# F4AIR.net
KiCad netlist of a schematic drawn in Altium Designer
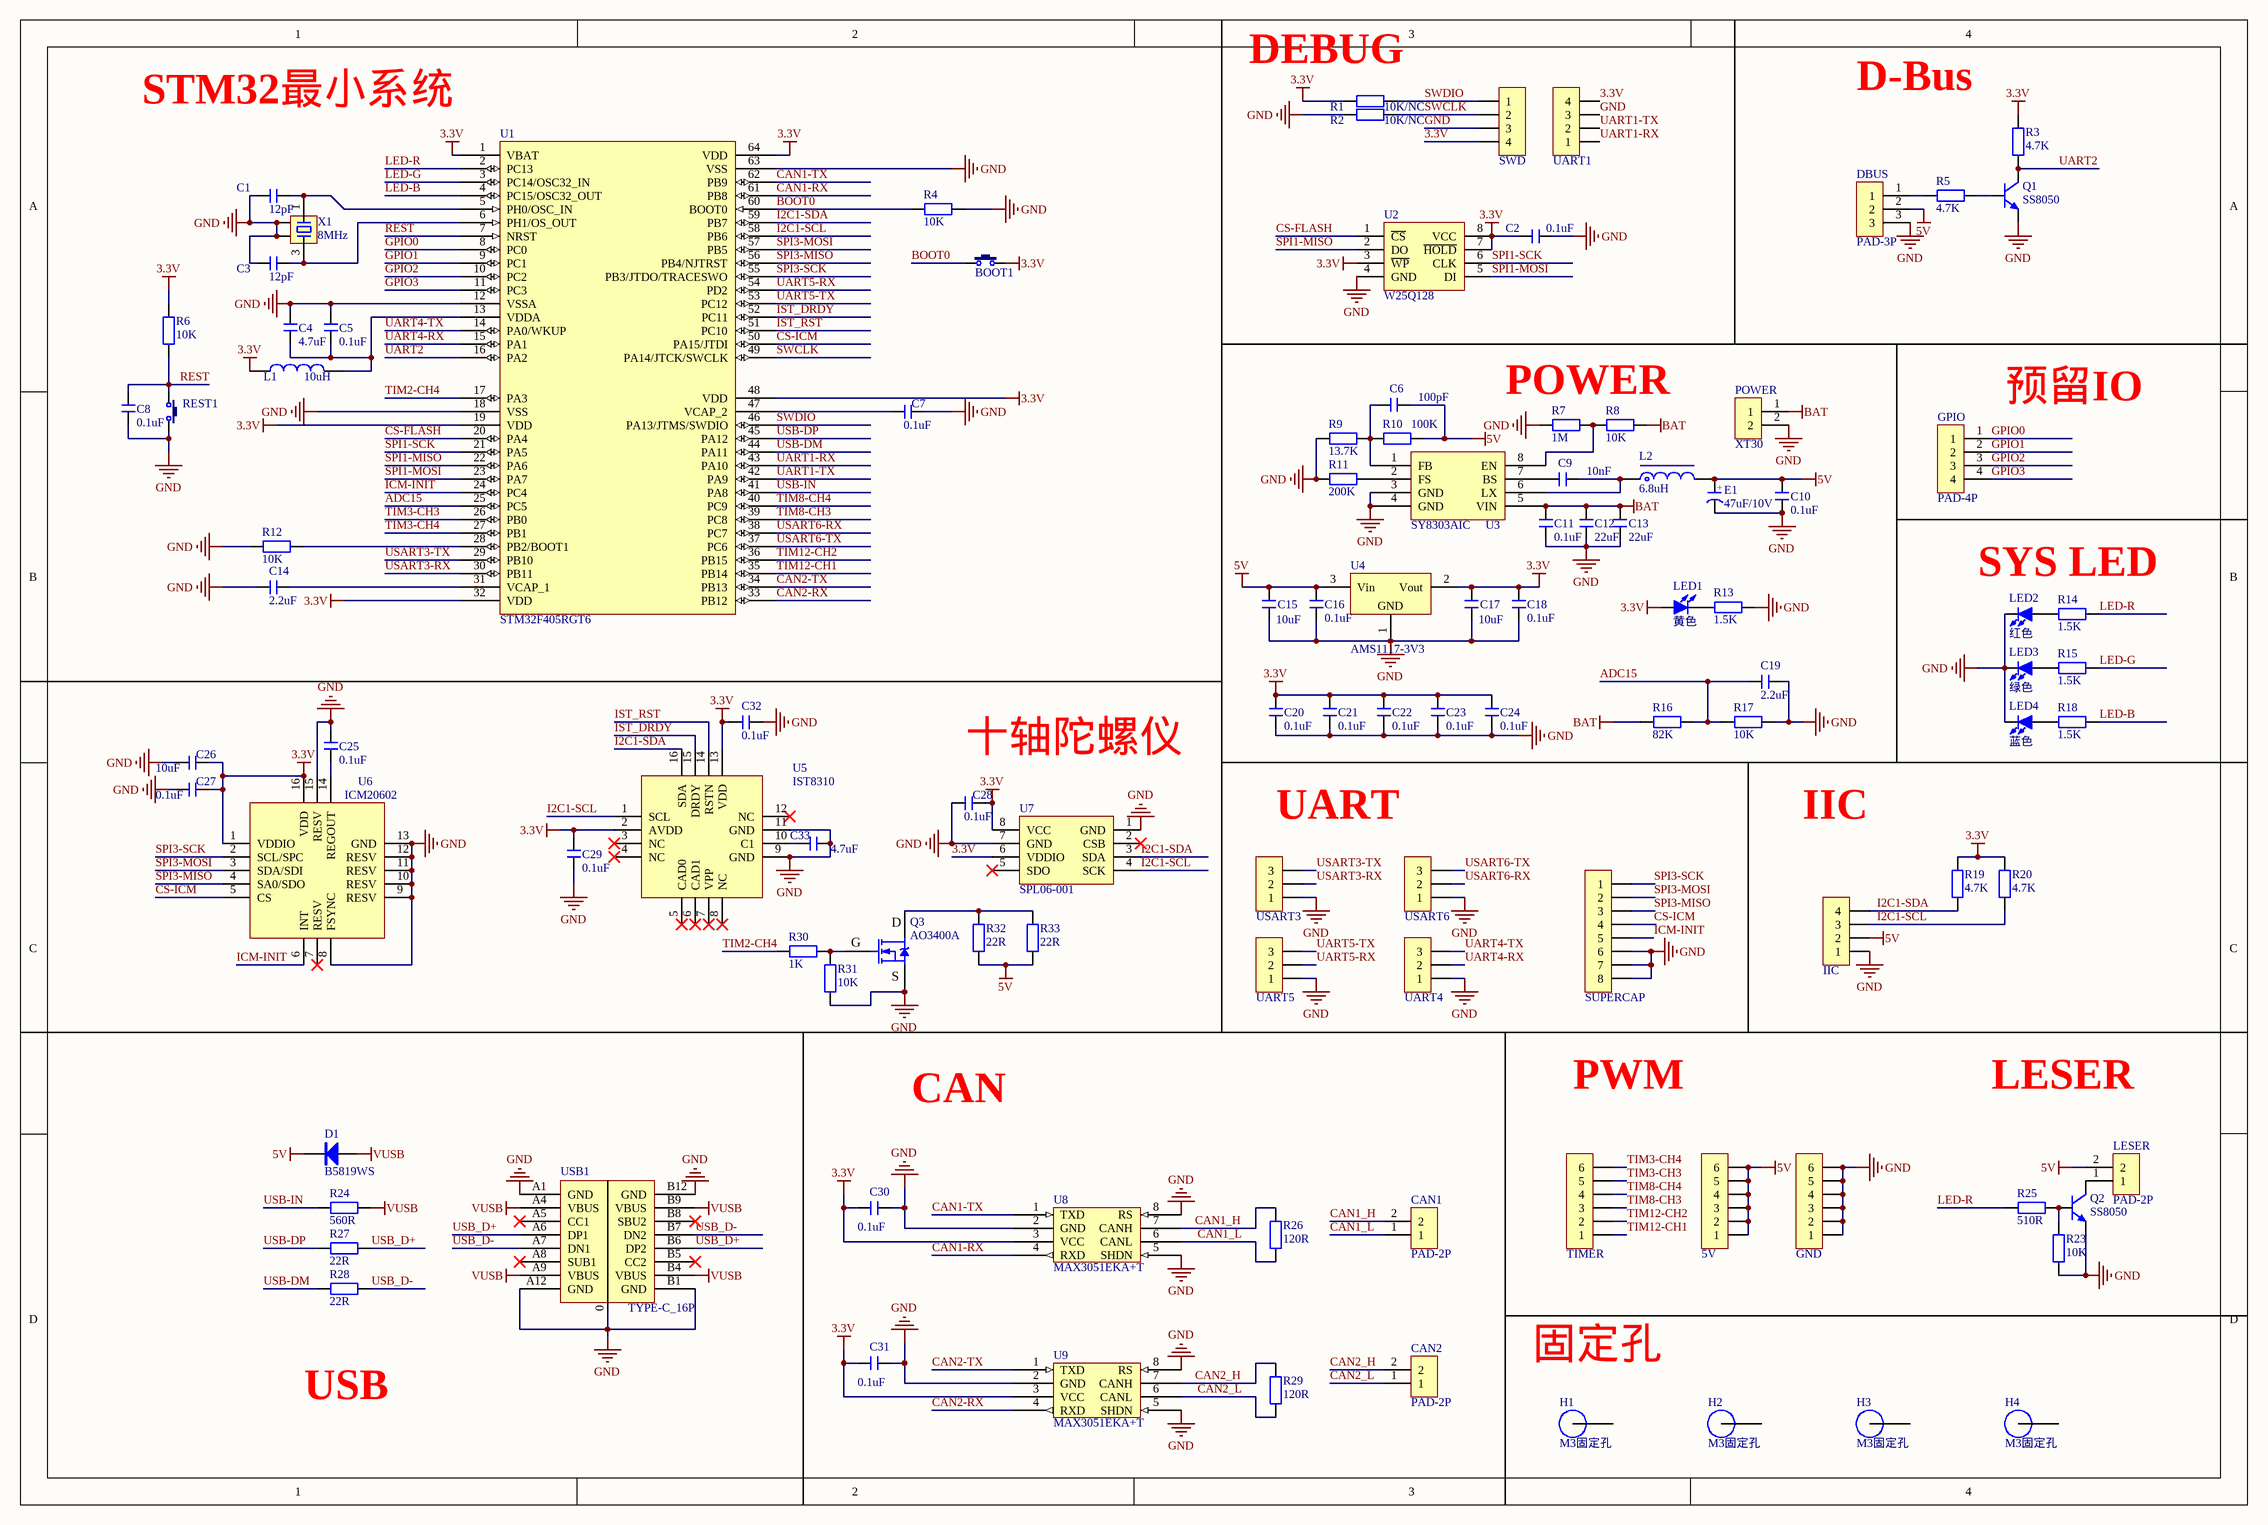
[diagram p0: F4AIR.SchDoc]

(export (version "E")
  (design (tool "Eeschema 10.0.6"))
  (components
    (comp (ref "5V")
      (value "HDR-1X6")
      (footprint "HDR2.54-LI-6P")
      (description "6P接插件")
      (libsource (lib "*") (part "Header 6"))
    )
    (comp (ref "BOOT1")
      (value "3x6x5")
      (footprint "TSW SMD-3*6*5")
      (description "3x6轻触开关")
      (libsource (lib "") (part "TSW 3x6_1"))
    )
    (comp (ref "C1")
      (value "12pF")
      (footprint "C 0603_M")
      (description "无极性贴片电容")
      (libsource (lib "Schlib1") (part "C"))
    )
    (comp (ref "C2")
      (value "0.1uF")
      (footprint "C 0603_M")
      (description "无极性贴片电容")
      (libsource (lib "Schlib") (part "C"))
    )
    (comp (ref "C3")
      (value "12pF")
      (footprint "C 0603_M")
      (description "无极性贴片电容")
      (libsource (lib "Schlib1") (part "C"))
    )
    (comp (ref "C4")
      (value "4.7uF")
      (footprint "C 0603_M")
      (description "无极性贴片电容")
      (libsource (lib "Schlib1") (part "C"))
    )
    (comp (ref "C5")
      (value "0.1uF")
      (footprint "C 0603_M")
      (description "无极性贴片电容")
      (libsource (lib "Schlib1") (part "C"))
    )
    (comp (ref "C6")
      (value "100pF")
      (footprint "C 0603_M")
      (description "无极性贴片电容")
      (libsource (lib "Schlib1") (part "C"))
    )
    (comp (ref "C7")
      (value "0.1uF")
      (footprint "C 0603_M")
      (description "无极性贴片电容")
      (libsource (lib "Schlib1") (part "C"))
    )
    (comp (ref "C8")
      (value "0.1uF")
      (footprint "C 0603_M")
      (description "无极性贴片电容")
      (libsource (lib "Schlib1") (part "C"))
    )
    (comp (ref "C9")
      (value "10nF")
      (footprint "C 0603_M")
      (description "无极性贴片电容")
      (libsource (lib "Schlib1") (part "C"))
    )
    (comp (ref "C10")
      (value "0.1uF")
      (footprint "C 0603_M")
      (description "无极性贴片电容")
      (libsource (lib "Schlib1") (part "C"))
    )
    (comp (ref "C11")
      (value "0.1uF")
      (footprint "C 0603_M")
      (description "无极性贴片电容")
      (libsource (lib "Schlib1") (part "C"))
    )
    (comp (ref "C12")
      (value "22uF")
      (footprint "C 1210_M")
      (description "无极性贴片电容")
      (libsource (lib "核心板v2") (part "C"))
    )
    (comp (ref "C13")
      (value "22uF")
      (footprint "C 1210_M")
      (description "无极性贴片电容")
      (libsource (lib "核心板v2") (part "C"))
    )
    (comp (ref "C14")
      (value "2.2uF")
      (footprint "C 0603_M")
      (description "无极性贴片电容")
      (libsource (lib "Schlib1") (part "C"))
    )
    (comp (ref "C15")
      (value "10uF")
      (footprint "C 0805_M")
      (description "无极性贴片电容")
      (libsource (lib "altium-import") (part "root_1_C_"))
    )
    (comp (ref "C16")
      (value "0.1uF")
      (footprint "C 0603_M")
      (description "无极性贴片电容")
      (libsource (lib "Schlib1") (part "C"))
    )
    (comp (ref "C17")
      (value "10uF")
      (footprint "C 0805_M")
      (description "无极性贴片电容")
      (libsource (lib "altium-import") (part "root_1_C_"))
    )
    (comp (ref "C18")
      (value "0.1uF")
      (footprint "C 0603_M")
      (description "无极性贴片电容")
      (libsource (lib "Schlib1") (part "C"))
    )
    (comp (ref "C19")
      (value "2.2uF")
      (footprint "C 0603_M")
      (description "无极性贴片电容")
      (libsource (lib "Schlib") (part "C"))
    )
    (comp (ref "C20")
      (value "0.1uF")
      (footprint "C 0603_M")
      (description "无极性贴片电容")
      (libsource (lib "Schlib1") (part "C"))
    )
    (comp (ref "C21")
      (value "0.1uF")
      (footprint "C 0603_M")
      (description "无极性贴片电容")
      (libsource (lib "Schlib1") (part "C"))
    )
    (comp (ref "C22")
      (value "0.1uF")
      (footprint "C 0603_M")
      (description "无极性贴片电容")
      (libsource (lib "Schlib1") (part "C"))
    )
    (comp (ref "C23")
      (value "0.1uF")
      (footprint "C 0603_M")
      (description "无极性贴片电容")
      (libsource (lib "Schlib1") (part "C"))
    )
    (comp (ref "C24")
      (value "0.1uF")
      (footprint "C 0603_M")
      (description "无极性贴片电容")
      (libsource (lib "Schlib1") (part "C"))
    )
    (comp (ref "C25")
      (value "0.1uF")
      (footprint "C 0603_M")
      (description "无极性贴片电容")
      (libsource (lib "Schlib1") (part "C"))
    )
    (comp (ref "C26")
      (value "10uF")
      (footprint "C 0805_M")
      (description "无极性贴片电容")
      (libsource (lib "Schlib1") (part "C"))
    )
    (comp (ref "C27")
      (value "0.1uF")
      (footprint "C 0603_M")
      (description "无极性贴片电容")
      (libsource (lib "Schlib1") (part "C"))
    )
    (comp (ref "C28")
      (value "0.1uF")
      (footprint "C 0603_M")
      (description "无极性贴片电容")
      (libsource (lib "Schlib1") (part "C"))
    )
    (comp (ref "C29")
      (value "0.1uF")
      (footprint "C 0603_M")
      (description "无极性贴片电容")
      (libsource (lib "Schlib1") (part "C"))
    )
    (comp (ref "C30")
      (value "0.1uF")
      (footprint "C 0603_M")
      (description "无极性贴片电容")
      (libsource (lib "Schlib1") (part "C"))
    )
    (comp (ref "C31")
      (value "0.1uF")
      (footprint "C 0603_M")
      (description "无极性贴片电容")
      (libsource (lib "Schlib1") (part "C"))
    )
    (comp (ref "C32")
      (value "0.1uF")
      (footprint "C 0603_M")
      (description "无极性贴片电容")
      (libsource (lib "Schlib1") (part "C"))
    )
    (comp (ref "C33")
      (value "4.7uF")
      (footprint "C 0603_M")
      (description "无极性贴片电容")
      (libsource (lib "Schlib1") (part "C"))
    )
    (comp (ref "CAN1") (value "PAD-2P") (footprint "MX 1.25-WS-2P") (libsource (lib "") (part "PAD-2P_1")))
    (comp (ref "CAN2") (value "PAD-2P") (footprint "MX 1.25-WS-2P") (libsource (lib "") (part "PAD-2P_1")))
    (comp (ref "D1")
      (value "B5819WS")
      (footprint "SOD-323")
      (description "肖特基二极管")
      (libsource (lib "Schlib") (part "SS54"))
    )
    (comp (ref "DBUS") (value "PAD-3P") (footprint "HDR2.54-WI-3P") (libsource (lib "F4AIR") (part "PAD-3P")))
    (comp (ref "E1")
      (value "47uF/10V")
      (footprint "CD A(3216)")
      (description "贴片钽电容")
      (libsource (lib "核心板v2") (part "C-CD"))
    )
    (comp (ref "GND")
      (value "HDR-1X6")
      (footprint "HDR2.54-LI-6P")
      (description "6P接插件")
      (libsource (lib "*") (part "Header 6"))
    )
    (comp (ref "GPIO") (value "PAD-4P") (footprint "PAD-1.25-4P") (libsource (lib "F4AIR") (part "PAD-4P")))
    (comp (ref "H1")
      (value "M3固定孔")
      (footprint "M3x4_N")
      (description "铜柱孔")
      (libsource (lib "F4AIR") (part "M3"))
    )
    (comp (ref "H2")
      (value "M3固定孔")
      (footprint "M3x4_N")
      (description "铜柱孔")
      (libsource (lib "F4AIR") (part "M3"))
    )
    (comp (ref "H3")
      (value "M3固定孔")
      (footprint "M3x4_N")
      (description "铜柱孔")
      (libsource (lib "F4AIR") (part "M3"))
    )
    (comp (ref "H4")
      (value "M3固定孔")
      (footprint "M3x4_N")
      (description "铜柱孔")
      (libsource (lib "F4AIR") (part "M3"))
    )
    (comp (ref "IIC")
      (value "HDR-1X4")
      (footprint "HDR2.54-LI-4P")
      (description "HDR 2.54 -4P")
      (libsource (lib "核心板v2") (part "HDR 2.54 -4P_1"))
    )
    (comp (ref "L1")
      (value "10uH")
      (footprint "L 0603")
      (description "小功率贴片电感")
      (libsource (lib "Schlib1") (part "L"))
    )
    (comp (ref "L2")
      (value "6.8uH")
      (footprint "L-SMD-0630")
      (description "贴片功率电感")
      (libsource (lib "核心板v2") (part "L-CD"))
    )
    (comp (ref "LED1")
      (value "黄色")
      (footprint "LED 0603Y")
      (description "贴片LED")
      (libsource (lib "核心板v2") (part "LED-SMD"))
    )
    (comp (ref "LED2")
      (value "红色")
      (footprint "LED 0603R")
      (description "贴片LED")
      (libsource (lib "核心板v2") (part "LED-SMD"))
    )
    (comp (ref "LED3")
      (value "绿色")
      (footprint "LED 0603G")
      (description "贴片LED")
      (libsource (lib "核心板v2") (part "LED-SMD"))
    )
    (comp (ref "LED4")
      (value "蓝色")
      (footprint "LED 0603B")
      (description "贴片LED")
      (libsource (lib "核心板v2") (part "LED-SMD"))
    )
    (comp (ref "LESER") (value "PAD-2P") (footprint "MX 1.25-WS-2P") (libsource (lib "") (part "PAD-2P_1")))
    (comp (ref "POWER") (value "XT30") (footprint "XT30-L") (libsource (lib "F4AIR") (part "PAD-2P")))
    (comp (ref "Q1")
      (value "SS8050")
      (footprint "SOT23-3M")
      (description "高频放大-NPN型")
      (libsource (lib "Schlib1") (part "8050-SMD"))
    )
    (comp (ref "Q2")
      (value "SS8050")
      (footprint "SOT23-3M")
      (description "高频放大-NPN型")
      (libsource (lib "核心板v2") (part "8050-SMD"))
    )
    (comp (ref "Q3") (value "AO3400A") (footprint "SOT23-3M") (libsource (lib "F4AIR") (part "AO3400A")))
    (comp (ref "R1")
      (value "10K/NC")
      (footprint "R 0603_M")
      (description "贴片电阻")
      (libsource (lib "Schlib1") (part "R"))
    )
    (comp (ref "R2")
      (value "10K/NC")
      (footprint "R 0603_M")
      (description "贴片电阻")
      (libsource (lib "Schlib1") (part "R"))
    )
    (comp (ref "R3")
      (value "4.7K")
      (footprint "R 0603_M")
      (description "贴片电阻")
      (libsource (lib "Schlib1") (part "R"))
    )
    (comp (ref "R4")
      (value "10K")
      (footprint "R 0603_M")
      (description "贴片电阻")
      (libsource (lib "Schlib1") (part "R"))
    )
    (comp (ref "R5")
      (value "4.7K")
      (footprint "R 0603_M")
      (description "贴片电阻")
      (libsource (lib "Schlib1") (part "R"))
    )
    (comp (ref "R6")
      (value "10K")
      (footprint "R 0603_M")
      (description "贴片电阻")
      (libsource (lib "Schlib1") (part "R"))
    )
    (comp (ref "R7")
      (value "1M")
      (footprint "R 0603_M")
      (description "贴片电阻")
      (libsource (lib "altium-import") (part "root_2_R_"))
    )
    (comp (ref "R8")
      (value "10K")
      (footprint "R 0603_M")
      (description "贴片电阻")
      (libsource (lib "altium-import") (part "root_2_R_"))
    )
    (comp (ref "R9")
      (value "13.7K")
      (footprint "R 0603_M")
      (description "贴片电阻")
      (libsource (lib "altium-import") (part "root_2_R_"))
    )
    (comp (ref "R10")
      (value "100K")
      (footprint "R 0603_M")
      (description "贴片电阻")
      (libsource (lib "altium-import") (part "root_2_R_"))
    )
    (comp (ref "R11")
      (value "200K")
      (footprint "R 0603_M")
      (description "贴片电阻")
      (libsource (lib "altium-import") (part "root_2_R_"))
    )
    (comp (ref "R12")
      (value "10K")
      (footprint "R 0603_M")
      (description "贴片电阻")
      (libsource (lib "Schlib1") (part "R"))
    )
    (comp (ref "R13")
      (value "1.5K")
      (footprint "R 0603_M")
      (description "贴片电阻")
      (libsource (lib "核心板v2") (part "R"))
    )
    (comp (ref "R14")
      (value "1.5K")
      (footprint "R 0603_M")
      (description "贴片电阻")
      (libsource (lib "核心板v2") (part "R"))
    )
    (comp (ref "R15")
      (value "1.5K")
      (footprint "R 0603_M")
      (description "贴片电阻")
      (libsource (lib "核心板v2") (part "R"))
    )
    (comp (ref "R16")
      (value "82K")
      (footprint "R 0603_M")
      (description "贴片电阻")
      (libsource (lib "Schlib") (part "R"))
    )
    (comp (ref "R17")
      (value "10K")
      (footprint "R 0603_M")
      (description "贴片电阻")
      (libsource (lib "Schlib") (part "R"))
    )
    (comp (ref "R18")
      (value "1.5K")
      (footprint "R 0603_M")
      (description "贴片电阻")
      (libsource (lib "核心板v2") (part "R"))
    )
    (comp (ref "R19")
      (value "4.7K")
      (footprint "R 0603_M")
      (description "贴片电阻")
      (libsource (lib "altium-import") (part "root_3_R_"))
    )
    (comp (ref "R20")
      (value "4.7K")
      (footprint "R 0603_M")
      (description "贴片电阻")
      (libsource (lib "altium-import") (part "root_1_R_"))
    )
    (comp (ref "R23")
      (value "10K")
      (footprint "R 0603_M")
      (description "贴片电阻")
      (libsource (lib "核心板v2") (part "R"))
    )
    (comp (ref "R24")
      (value "560R")
      (footprint "R 0603_M")
      (description "贴片电阻")
      (libsource (lib "Schlib1") (part "R"))
    )
    (comp (ref "R25")
      (value "510R")
      (footprint "R 0603_M")
      (description "贴片电阻")
      (libsource (lib "核心板v2") (part "R"))
    )
    (comp (ref "R26")
      (value "120R")
      (footprint "R 0603_M")
      (description "贴片电阻")
      (libsource (lib "altium-import") (part "root_1_R_"))
    )
    (comp (ref "R27")
      (value "22R")
      (footprint "R 0603_M")
      (description "贴片电阻")
      (libsource (lib "Schlib") (part "R"))
    )
    (comp (ref "R28")
      (value "22R")
      (footprint "R 0603_M")
      (description "贴片电阻")
      (libsource (lib "Schlib") (part "R"))
    )
    (comp (ref "R29")
      (value "120R")
      (footprint "R 0603_M")
      (description "贴片电阻")
      (libsource (lib "altium-import") (part "root_1_R_"))
    )
    (comp (ref "R30")
      (value "1K")
      (footprint "R 0603_M")
      (description "贴片电阻")
      (libsource (lib "F4AIR") (part "R"))
    )
    (comp (ref "R31")
      (value "10K")
      (footprint "R 0603_M")
      (description "贴片电阻")
      (libsource (lib "F4AIR") (part "R"))
    )
    (comp (ref "R32")
      (value "22R")
      (footprint "R 0603_M")
      (description "贴片电阻")
      (libsource (lib "F4AIR") (part "R"))
    )
    (comp (ref "R33")
      (value "22R")
      (footprint "R 0603_M")
      (description "贴片电阻")
      (libsource (lib "F4AIR") (part "R"))
    )
    (comp (ref "REST1")
      (value "3x6x5")
      (footprint "TSW SMD-3*6*5")
      (description "3x6轻触开关")
      (libsource (lib "Schlib1") (part "TSW 3x6"))
    )
    (comp (ref "SUPERCAP")
      (value "HDR-1X8")
      (footprint "MX 1.25-WS-6P")
      (description "HDR 2.54 -8P")
      (libsource (lib "cap") (part "HDR 2.54 -8P"))
    )
    (comp (ref "SWD")
      (value "HDR-1X4")
      (footprint "MX 1.25-WS-4P")
      (description "MX 1.25 -4P")
      (libsource (lib "Schlib1") (part "MX 1.25 -4P"))
    )
    (comp (ref "TIMER")
      (value "HDR-1X6")
      (footprint "HDR2.54-LI-6P")
      (description "6P接插件")
      (libsource (lib "*") (part "Header 6"))
    )
    (comp (ref "U1")
      (value "STM32F405RGT6")
      (footprint "LQFP64")
      (libsource (lib "Schlib") (part "STM32F405RGT6"))
    )
    (comp (ref "U2")
      (value "W25Q128")
      (footprint "SOP8_M - 208mil")
      (libsource (lib "Schlib") (part "W25Q128"))
    )
    (comp (ref "U3")
      (value "SY8303AIC")
      (footprint "SOT23-8")
      (description "DCDC降压芯片")
      (libsource (lib "核心板v2") (part "SY8303AIC"))
    )
    (comp (ref "U4")
      (value "AMS1117-3V3")
      (footprint "SOT-89")
      (description "三端稳压芯片")
      (libsource (lib "F4AIR") (part "AMS1117"))
    )
    (comp (ref "U5")
      (value "IST8310")
      (footprint "LGA16 3x3")
      (description "三轴电子罗盘")
      (libsource (lib "F4AIR") (part "IST8310"))
    )
    (comp (ref "U6") (value "ICM20602") (footprint "LGA16") (libsource (lib "Schlib1") (part "ICM20602")))
    (comp (ref "U7") (value "SPL06-001") (footprint "LGA08") (libsource (lib "Schlib1") (part "SPL06")))
    (comp (ref "U8")
      (value "MAX3051EKA+T")
      (footprint "SOT23-8")
      (description "CAN芯片")
      (libsource (lib "核心板v2") (part "MAX3051EKA+T"))
    )
    (comp (ref "U9")
      (value "MAX3051EKA+T")
      (footprint "SOT23-8")
      (description "CAN芯片")
      (libsource (lib "核心板v2") (part "MAX3051EKA+T"))
    )
    (comp (ref "UART1")
      (value "HDR-1X4")
      (footprint "MX 1.25-WS-4P")
      (description "HDR 2.54 -4P")
      (libsource (lib "核心板v2") (part "HDR 2.54 -4P_1"))
    )
    (comp (ref "UART4")
      (value "HDR-1X3")
      (footprint "MX 1.25-WS-3P")
      (description "HDR 2.54 -3P")
      (libsource (lib "Schlib1") (part "HDR 2.54 -3P"))
    )
    (comp (ref "UART5")
      (value "HDR-1X3")
      (footprint "MX 1.25-WS-3P")
      (description "HDR 2.54 -3P")
      (libsource (lib "Schlib1") (part "HDR 2.54 -3P"))
    )
    (comp (ref "USART3")
      (value "HDR-1X3")
      (footprint "MX 1.25-WS-3P")
      (description "HDR 2.54 -3P")
      (libsource (lib "Schlib1") (part "HDR 2.54 -3P"))
    )
    (comp (ref "USART6")
      (value "HDR-1X3")
      (footprint "MX 1.25-WS-3P")
      (description "HDR 2.54 -3P")
      (libsource (lib "Schlib1") (part "HDR 2.54 -3P"))
    )
    (comp (ref "USB1")
      (value "TYPE-C_16P")
      (footprint "Type-C_16p")
      (libsource (lib "Schlib") (part "TYPE-C_16P"))
    )
    (comp (ref "X1")
      (value "8MHz")
      (footprint "OSC 3225-4P")
      (description "4脚无源晶振")
      (libsource (lib "Schlib1") (part "XTAL-4P"))
    )
  )
  (nets
    (net (code "1") (name "/ADC15") (class "Default")
      (node (ref "C19") (pin "1") (pinfunction "1_1") (pintype "passive"))
      (node (ref "R16") (pin "2") (pinfunction "2_2") (pintype "passive"))
      (node (ref "R17") (pin "1") (pinfunction "1_1") (pintype "passive"))
      (node (ref "U1") (pin "25") (pinfunction "PC5_25") (pintype "bidirectional"))
    )
    (net (code "2") (name "/BOOT0") (class "Default")
      (node (ref "BOOT1") (pin "1") (pinfunction "1_1") (pintype "passive"))
      (node (ref "R4") (pin "1") (pinfunction "1_1") (pintype "passive"))
      (node (ref "U1") (pin "60") (pinfunction "BOOT0_60") (pintype "input"))
    )
    (net (code "3") (name "/CAN1-RX") (class "Default")
      (node (ref "U1") (pin "61") (pinfunction "PB8_61") (pintype "bidirectional"))
      (node (ref "U8") (pin "4") (pinfunction "RXD_4") (pintype "output"))
    )
    (net (code "4") (name "/CAN1-TX") (class "Default")
      (node (ref "U1") (pin "62") (pinfunction "PB9_62") (pintype "bidirectional"))
      (node (ref "U8") (pin "1") (pinfunction "TXD_1") (pintype "input"))
    )
    (net (code "5") (name "/CAN1_H") (class "Default")
      (node (ref "CAN1") (pin "2") (pinfunction "2_2") (pintype "passive"))
      (node (ref "R26") (pin "2") (pinfunction "2_2") (pintype "passive"))
      (node (ref "U8") (pin "7") (pinfunction "CANH_7") (pintype "passive"))
    )
    (net (code "6") (name "/CAN1_L") (class "Default")
      (node (ref "CAN1") (pin "1") (pinfunction "1_1") (pintype "passive"))
      (node (ref "R26") (pin "1") (pinfunction "1_1") (pintype "passive"))
      (node (ref "U8") (pin "6") (pinfunction "CANL_6") (pintype "passive"))
    )
    (net (code "7") (name "/CAN2-RX") (class "Default")
      (node (ref "U1") (pin "33") (pinfunction "PB12_33") (pintype "bidirectional"))
      (node (ref "U9") (pin "4") (pinfunction "RXD_4") (pintype "output"))
    )
    (net (code "8") (name "/CAN2-TX") (class "Default")
      (node (ref "U1") (pin "34") (pinfunction "PB13_34") (pintype "bidirectional"))
      (node (ref "U9") (pin "1") (pinfunction "TXD_1") (pintype "input"))
    )
    (net (code "9") (name "/CAN2_H") (class "Default")
      (node (ref "CAN2") (pin "2") (pinfunction "2_2") (pintype "passive"))
      (node (ref "R29") (pin "2") (pinfunction "2_2") (pintype "passive"))
      (node (ref "U9") (pin "7") (pinfunction "CANH_7") (pintype "passive"))
    )
    (net (code "10") (name "/CAN2_L") (class "Default")
      (node (ref "CAN2") (pin "1") (pinfunction "1_1") (pintype "passive"))
      (node (ref "R29") (pin "1") (pinfunction "1_1") (pintype "passive"))
      (node (ref "U9") (pin "6") (pinfunction "CANL_6") (pintype "passive"))
    )
    (net (code "11") (name "/CS-FLASH") (class "Default")
      (node (ref "U1") (pin "20") (pinfunction "PA4_20") (pintype "bidirectional"))
      (node (ref "U2") (pin "1") (pinfunction "~{CS}_1") (pintype "passive"))
    )
    (net (code "12") (name "/CS-ICM") (class "Default")
      (node (ref "SUPERCAP") (pin "4") (pinfunction "4_4") (pintype "passive"))
      (node (ref "U1") (pin "50") (pinfunction "PA15/JTDI_50") (pintype "bidirectional"))
      (node (ref "U6") (pin "5") (pinfunction "CS_5") (pintype "passive"))
    )
    (net (code "13") (name "/GPIO0") (class "Default")
      (node (ref "GPIO") (pin "1") (pinfunction "1_1") (pintype "passive"))
      (node (ref "U1") (pin "8") (pinfunction "PC0_8") (pintype "bidirectional"))
    )
    (net (code "14") (name "/GPIO1") (class "Default")
      (node (ref "GPIO") (pin "2") (pinfunction "2_2") (pintype "passive"))
      (node (ref "U1") (pin "9") (pinfunction "PC1_9") (pintype "bidirectional"))
    )
    (net (code "15") (name "/GPIO2") (class "Default")
      (node (ref "GPIO") (pin "3") (pinfunction "3_3") (pintype "passive"))
      (node (ref "U1") (pin "10") (pinfunction "PC2_10") (pintype "bidirectional"))
    )
    (net (code "16") (name "/GPIO3") (class "Default")
      (node (ref "GPIO") (pin "4") (pinfunction "4_4") (pintype "passive"))
      (node (ref "U1") (pin "11") (pinfunction "PC3_11") (pintype "bidirectional"))
    )
    (net (code "17") (name "/I2C1-SCL") (class "Default")
      (node (ref "IIC") (pin "3") (pinfunction "3_3") (pintype "passive"))
      (node (ref "R20") (pin "1") (pinfunction "1_1") (pintype "passive"))
      (node (ref "U1") (pin "58") (pinfunction "PB6_58") (pintype "bidirectional"))
      (node (ref "U5") (pin "1") (pinfunction "SCL_1") (pintype "passive"))
      (node (ref "U7") (pin "4") (pinfunction "SCK_4") (pintype "passive"))
    )
    (net (code "18") (name "/I2C1-SDA") (class "Default")
      (node (ref "IIC") (pin "4") (pinfunction "4_4") (pintype "passive"))
      (node (ref "R19") (pin "2") (pinfunction "2_2") (pintype "passive"))
      (node (ref "U1") (pin "59") (pinfunction "PB7_59") (pintype "bidirectional"))
      (node (ref "U5") (pin "16") (pinfunction "SDA_16") (pintype "passive"))
      (node (ref "U7") (pin "3") (pinfunction "SDA_3") (pintype "passive"))
    )
    (net (code "19") (name "/ICM-INIT") (class "Default")
      (node (ref "SUPERCAP") (pin "5") (pinfunction "5_5") (pintype "passive"))
      (node (ref "U1") (pin "24") (pinfunction "PC4_24") (pintype "bidirectional"))
      (node (ref "U6") (pin "6") (pinfunction "INT_6") (pintype "passive"))
    )
    (net (code "20") (name "/IST_DRDY") (class "Default")
      (node (ref "U1") (pin "52") (pinfunction "PC11_52") (pintype "bidirectional"))
      (node (ref "U5") (pin "15") (pinfunction "DRDY_15") (pintype "passive"))
    )
    (net (code "21") (name "/IST_RST") (class "Default")
      (node (ref "U1") (pin "51") (pinfunction "PC10_51") (pintype "bidirectional"))
      (node (ref "U5") (pin "14") (pinfunction "RSTN_14") (pintype "passive"))
    )
    (net (code "22") (name "/LED-B") (class "Default")
      (node (ref "R18") (pin "2") (pinfunction "2_2") (pintype "passive"))
      (node (ref "U1") (pin "4") (pinfunction "PC15/OSC32_OUT_4") (pintype "bidirectional"))
    )
    (net (code "23") (name "/LED-G") (class "Default")
      (node (ref "R15") (pin "2") (pinfunction "2_2") (pintype "passive"))
      (node (ref "U1") (pin "3") (pinfunction "PC14/OSC32_IN_3") (pintype "bidirectional"))
    )
    (net (code "24") (name "/LED-R") (class "Default")
      (node (ref "R14") (pin "2") (pinfunction "2_2") (pintype "passive"))
      (node (ref "R25") (pin "1") (pinfunction "1_1") (pintype "passive"))
      (node (ref "U1") (pin "2") (pinfunction "PC13_2") (pintype "bidirectional"))
    )
    (net (code "25") (name "/REST") (class "Default")
      (node (ref "C8") (pin "2") (pinfunction "2_2") (pintype "passive"))
      (node (ref "R6") (pin "1") (pinfunction "1_1") (pintype "passive"))
      (node (ref "REST1") (pin "1") (pinfunction "1_1") (pintype "passive"))
      (node (ref "U1") (pin "7") (pinfunction "NRST_7") (pintype "input"))
    )
    (net (code "26") (name "/SPI1-MISO") (class "Default")
      (node (ref "U1") (pin "22") (pinfunction "PA6_22") (pintype "bidirectional"))
      (node (ref "U2") (pin "2") (pinfunction "DO_2") (pintype "passive"))
    )
    (net (code "27") (name "/SPI1-MOSI") (class "Default")
      (node (ref "U1") (pin "23") (pinfunction "PA7_23") (pintype "bidirectional"))
      (node (ref "U2") (pin "5") (pinfunction "DI_5") (pintype "passive"))
    )
    (net (code "28") (name "/SPI1-SCK") (class "Default")
      (node (ref "U1") (pin "21") (pinfunction "PA5_21") (pintype "bidirectional"))
      (node (ref "U2") (pin "6") (pinfunction "CLK_6") (pintype "passive"))
    )
    (net (code "29") (name "/SPI3-MISO") (class "Default")
      (node (ref "SUPERCAP") (pin "3") (pinfunction "3_3") (pintype "passive"))
      (node (ref "U1") (pin "56") (pinfunction "PB4/NJTRST_56") (pintype "bidirectional"))
      (node (ref "U6") (pin "4") (pinfunction "SA0/SDO_4") (pintype "passive"))
    )
    (net (code "30") (name "/SPI3-MOSI") (class "Default")
      (node (ref "SUPERCAP") (pin "2") (pinfunction "2_2") (pintype "passive"))
      (node (ref "U1") (pin "57") (pinfunction "PB5_57") (pintype "bidirectional"))
      (node (ref "U6") (pin "3") (pinfunction "SDA/SDI_3") (pintype "passive"))
    )
    (net (code "31") (name "/SPI3-SCK") (class "Default")
      (node (ref "SUPERCAP") (pin "1") (pinfunction "1_1") (pintype "passive"))
      (node (ref "U1") (pin "55") (pinfunction "PB3/JTDO/TRACESWO_55") (pintype "bidirectional"))
      (node (ref "U6") (pin "2") (pinfunction "SCL/SPC_2") (pintype "passive"))
    )
    (net (code "32") (name "/SWCLK") (class "Default")
      (node (ref "R2") (pin "2") (pinfunction "2_2") (pintype "passive"))
      (node (ref "SWD") (pin "2") (pinfunction "2_2") (pintype "passive"))
      (node (ref "U1") (pin "49") (pinfunction "PA14/JTCK/SWCLK_49") (pintype "bidirectional"))
    )
    (net (code "33") (name "/SWDIO") (class "Default")
      (node (ref "R1") (pin "2") (pinfunction "2_2") (pintype "passive"))
      (node (ref "SWD") (pin "1") (pinfunction "1_1") (pintype "passive"))
      (node (ref "U1") (pin "46") (pinfunction "PA13/JTMS/SWDIO_46") (pintype "bidirectional"))
    )
    (net (code "34") (name "/TIM2-CH4") (class "Default")
      (node (ref "R30") (pin "1") (pinfunction "1_1") (pintype "passive"))
      (node (ref "U1") (pin "17") (pinfunction "PA3_17") (pintype "bidirectional"))
    )
    (net (code "35") (name "/TIM3-CH3") (class "Default")
      (node (ref "TIMER") (pin "5") (pinfunction "5_5") (pintype "passive"))
      (node (ref "U1") (pin "26") (pinfunction "PB0_26") (pintype "bidirectional"))
    )
    (net (code "36") (name "/TIM3-CH4") (class "Default")
      (node (ref "TIMER") (pin "6") (pinfunction "6_6") (pintype "passive"))
      (node (ref "U1") (pin "27") (pinfunction "PB1_27") (pintype "bidirectional"))
    )
    (net (code "37") (name "/TIM8-CH3") (class "Default")
      (node (ref "TIMER") (pin "3") (pinfunction "3_3") (pintype "passive"))
      (node (ref "U1") (pin "39") (pinfunction "PC8_39") (pintype "bidirectional"))
    )
    (net (code "38") (name "/TIM8-CH4") (class "Default")
      (node (ref "TIMER") (pin "4") (pinfunction "4_4") (pintype "passive"))
      (node (ref "U1") (pin "40") (pinfunction "PC9_40") (pintype "bidirectional"))
    )
    (net (code "39") (name "/TIM12-CH1") (class "Default")
      (node (ref "TIMER") (pin "1") (pinfunction "1_1") (pintype "passive"))
      (node (ref "U1") (pin "35") (pinfunction "PB14_35") (pintype "bidirectional"))
    )
    (net (code "40") (name "/TIM12-CH2") (class "Default")
      (node (ref "TIMER") (pin "2") (pinfunction "2_2") (pintype "passive"))
      (node (ref "U1") (pin "36") (pinfunction "PB15_36") (pintype "bidirectional"))
    )
    (net (code "41") (name "/UART1-RX") (class "Default")
      (node (ref "U1") (pin "43") (pinfunction "PA10_43") (pintype "bidirectional"))
      (node (ref "UART1") (pin "1") (pinfunction "1_1") (pintype "passive"))
    )
    (net (code "42") (name "/UART1-TX") (class "Default")
      (node (ref "U1") (pin "42") (pinfunction "PA9_42") (pintype "bidirectional"))
      (node (ref "UART1") (pin "2") (pinfunction "2_2") (pintype "passive"))
    )
    (net (code "43") (name "/UART2") (class "Default")
      (node (ref "Q1") (pin "3") (pinfunction "C_3") (pintype "passive"))
      (node (ref "R3") (pin "1") (pinfunction "1_1") (pintype "passive"))
      (node (ref "U1") (pin "16") (pinfunction "PA2_16") (pintype "bidirectional"))
    )
    (net (code "44") (name "/UART4-RX") (class "Default")
      (node (ref "U1") (pin "15") (pinfunction "PA1_15") (pintype "bidirectional"))
      (node (ref "UART4") (pin "2") (pinfunction "2_2") (pintype "passive"))
    )
    (net (code "45") (name "/UART4-TX") (class "Default")
      (node (ref "U1") (pin "14") (pinfunction "PA0/WKUP_14") (pintype "bidirectional"))
      (node (ref "UART4") (pin "3") (pinfunction "3_3") (pintype "passive"))
    )
    (net (code "46") (name "/UART5-RX") (class "Default")
      (node (ref "U1") (pin "54") (pinfunction "PD2_54") (pintype "bidirectional"))
      (node (ref "UART5") (pin "2") (pinfunction "2_2") (pintype "passive"))
    )
    (net (code "47") (name "/UART5-TX") (class "Default")
      (node (ref "U1") (pin "53") (pinfunction "PC12_53") (pintype "bidirectional"))
      (node (ref "UART5") (pin "3") (pinfunction "3_3") (pintype "passive"))
    )
    (net (code "48") (name "/USART3-RX") (class "Default")
      (node (ref "U1") (pin "30") (pinfunction "PB11_30") (pintype "bidirectional"))
      (node (ref "USART3") (pin "2") (pinfunction "2_2") (pintype "passive"))
    )
    (net (code "49") (name "/USART3-TX") (class "Default")
      (node (ref "U1") (pin "29") (pinfunction "PB10_29") (pintype "bidirectional"))
      (node (ref "USART3") (pin "3") (pinfunction "3_3") (pintype "passive"))
    )
    (net (code "50") (name "/USART6-RX") (class "Default")
      (node (ref "U1") (pin "38") (pinfunction "PC7_38") (pintype "bidirectional"))
      (node (ref "USART6") (pin "2") (pinfunction "2_2") (pintype "passive"))
    )
    (net (code "51") (name "/USART6-TX") (class "Default")
      (node (ref "U1") (pin "37") (pinfunction "PC6_37") (pintype "bidirectional"))
      (node (ref "USART6") (pin "3") (pinfunction "3_3") (pintype "passive"))
    )
    (net (code "52") (name "/USB-DM") (class "Default")
      (node (ref "R28") (pin "1") (pinfunction "1_1") (pintype "passive"))
      (node (ref "U1") (pin "44") (pinfunction "PA11_44") (pintype "bidirectional"))
    )
    (net (code "53") (name "/USB-DP") (class "Default")
      (node (ref "R27") (pin "1") (pinfunction "1_1") (pintype "passive"))
      (node (ref "U1") (pin "45") (pinfunction "PA12_45") (pintype "bidirectional"))
    )
    (net (code "54") (name "/USB-IN") (class "Default")
      (node (ref "R24") (pin "1") (pinfunction "1_1") (pintype "passive"))
      (node (ref "U1") (pin "41") (pinfunction "PA8_41") (pintype "bidirectional"))
    )
    (net (code "55") (name "/USB_D+") (class "Default")
      (node (ref "R27") (pin "2") (pinfunction "2_2") (pintype "passive"))
      (node (ref "USB1") (pin "A6") (pinfunction "DP1_A6") (pintype "passive"))
      (node (ref "USB1") (pin "B6") (pinfunction "DP2_B6") (pintype "passive"))
    )
    (net (code "56") (name "/USB_D-") (class "Default")
      (node (ref "R28") (pin "2") (pinfunction "2_2") (pintype "passive"))
      (node (ref "USB1") (pin "A7") (pinfunction "DN1_A7") (pintype "passive"))
      (node (ref "USB1") (pin "B7") (pinfunction "DN2_B7") (pintype "passive"))
    )
    (net (code "57") (name "3.3V") (class "Default")
      (node (ref "BOOT1") (pin "2") (pinfunction "2_2") (pintype "passive"))
      (node (ref "C17") (pin "2") (pinfunction "2_2") (pintype "passive"))
      (node (ref "C18") (pin "1") (pinfunction "1_1") (pintype "passive"))
      (node (ref "C2") (pin "1") (pinfunction "1_1") (pintype "passive"))
      (node (ref "C20") (pin "1") (pinfunction "1_1") (pintype "passive"))
      (node (ref "C21") (pin "1") (pinfunction "1_1") (pintype "passive"))
      (node (ref "C22") (pin "1") (pinfunction "1_1") (pintype "passive"))
      (node (ref "C23") (pin "1") (pinfunction "1_1") (pintype "passive"))
      (node (ref "C24") (pin "1") (pinfunction "1_1") (pintype "passive"))
      (node (ref "C26") (pin "2") (pinfunction "2_2") (pintype "passive"))
      (node (ref "C27") (pin "2") (pinfunction "2_2") (pintype "passive"))
      (node (ref "C28") (pin "2") (pinfunction "2_2") (pintype "passive"))
      (node (ref "C29") (pin "2") (pinfunction "2_2") (pintype "passive"))
      (node (ref "C30") (pin "2") (pinfunction "2_2") (pintype "passive"))
      (node (ref "C31") (pin "2") (pinfunction "2_2") (pintype "passive"))
      (node (ref "C32") (pin "2") (pinfunction "2_2") (pintype "passive"))
      (node (ref "L1") (pin "1") (pinfunction "1_1") (pintype "passive"))
      (node (ref "LED1") (pin "1") (pinfunction "A_1") (pintype "passive"))
      (node (ref "R1") (pin "1") (pinfunction "1_1") (pintype "passive"))
      (node (ref "R19") (pin "1") (pinfunction "1_1") (pintype "passive"))
      (node (ref "R20") (pin "2") (pinfunction "2_2") (pintype "passive"))
      (node (ref "R3") (pin "2") (pinfunction "2_2") (pintype "passive"))
      (node (ref "R6") (pin "2") (pinfunction "2_2") (pintype "passive"))
      (node (ref "SWD") (pin "4") (pinfunction "4_4") (pintype "passive"))
      (node (ref "U1") (pin "1") (pinfunction "VBAT_1") (pintype "power_in"))
      (node (ref "U1") (pin "19") (pinfunction "VDD_19") (pintype "power_in"))
      (node (ref "U1") (pin "32") (pinfunction "VDD_32") (pintype "power_in"))
      (node (ref "U1") (pin "48") (pinfunction "VDD_48") (pintype "power_in"))
      (node (ref "U1") (pin "64") (pinfunction "VDD_64") (pintype "power_in"))
      (node (ref "U2") (pin "3") (pinfunction "~{WP}_3") (pintype "passive"))
      (node (ref "U2") (pin "7") (pinfunction "~{HOLD}_7") (pintype "passive"))
      (node (ref "U2") (pin "8") (pinfunction "VCC_8") (pintype "passive"))
      (node (ref "U4") (pin "2") (pinfunction "Vout_2") (pintype "passive"))
      (node (ref "U5") (pin "13") (pinfunction "VDD_13") (pintype "passive"))
      (node (ref "U5") (pin "2") (pinfunction "AVDD_2") (pintype "passive"))
      (node (ref "U6") (pin "1") (pinfunction "VDDIO_1") (pintype "passive"))
      (node (ref "U6") (pin "16") (pinfunction "VDD_16") (pintype "passive"))
      (node (ref "U7") (pin "6") (pinfunction "VDDIO_6") (pintype "passive"))
      (node (ref "U7") (pin "8") (pinfunction "VCC_8") (pintype "passive"))
      (node (ref "U8") (pin "3") (pinfunction "VCC_3") (pintype "power_in"))
      (node (ref "U9") (pin "3") (pinfunction "VCC_3") (pintype "power_in"))
      (node (ref "UART1") (pin "4") (pinfunction "4_4") (pintype "passive"))
    )
    (net (code "58") (name "5V") (class "Default")
      (node (ref "5V") (pin "1") (pinfunction "1_1") (pintype "passive"))
      (node (ref "5V") (pin "2") (pinfunction "2_2") (pintype "passive"))
      (node (ref "5V") (pin "3") (pinfunction "3_3") (pintype "passive"))
      (node (ref "5V") (pin "4") (pinfunction "4_4") (pintype "passive"))
      (node (ref "5V") (pin "5") (pinfunction "5_5") (pintype "passive"))
      (node (ref "5V") (pin "6") (pinfunction "6_6") (pintype "passive"))
      (node (ref "C10") (pin "1") (pinfunction "1_1") (pintype "passive"))
      (node (ref "C15") (pin "2") (pinfunction "2_2") (pintype "passive"))
      (node (ref "C16") (pin "1") (pinfunction "1_1") (pintype "passive"))
      (node (ref "C6") (pin "1") (pinfunction "1_1") (pintype "passive"))
      (node (ref "D1") (pin "2") (pinfunction "K_2") (pintype "passive"))
      (node (ref "DBUS") (pin "2") (pinfunction "2_2") (pintype "passive"))
      (node (ref "E1") (pin "1") (pinfunction "A_1") (pintype "passive"))
      (node (ref "IIC") (pin "2") (pinfunction "2_2") (pintype "passive"))
      (node (ref "L2") (pin "2") (pinfunction "2_2") (pintype "passive"))
      (node (ref "LESER") (pin "2") (pinfunction "2_2") (pintype "passive"))
      (node (ref "R10") (pin "1") (pinfunction "1_1") (pintype "passive"))
      (node (ref "R32") (pin "1") (pinfunction "1_1") (pintype "passive"))
      (node (ref "R33") (pin "1") (pinfunction "1_1") (pintype "passive"))
      (node (ref "U4") (pin "3") (pinfunction "Vin_3") (pintype "passive"))
    )
    (net (code "59") (name "BAT") (class "Default")
      (node (ref "C11") (pin "1") (pinfunction "1_1") (pintype "passive"))
      (node (ref "C12") (pin "2") (pinfunction "2_2") (pintype "passive"))
      (node (ref "C13") (pin "2") (pinfunction "2_2") (pintype "passive"))
      (node (ref "POWER") (pin "1") (pinfunction "1_1") (pintype "passive"))
      (node (ref "R16") (pin "1") (pinfunction "1_1") (pintype "passive"))
      (node (ref "R8") (pin "1") (pinfunction "1_1") (pintype "passive"))
      (node (ref "U3") (pin "5") (pinfunction "VIN_5") (pintype "passive"))
    )
    (net (code "60") (name "GND") (class "Default")
      (node (ref "C1") (pin "1") (pinfunction "1_1") (pintype "passive"))
      (node (ref "C10") (pin "2") (pinfunction "2_2") (pintype "passive"))
      (node (ref "C11") (pin "2") (pinfunction "2_2") (pintype "passive"))
      (node (ref "C12") (pin "1") (pinfunction "1_1") (pintype "passive"))
      (node (ref "C13") (pin "1") (pinfunction "1_1") (pintype "passive"))
      (node (ref "C14") (pin "1") (pinfunction "1_1") (pintype "passive"))
      (node (ref "C15") (pin "1") (pinfunction "1_1") (pintype "passive"))
      (node (ref "C16") (pin "2") (pinfunction "2_2") (pintype "passive"))
      (node (ref "C17") (pin "1") (pinfunction "1_1") (pintype "passive"))
      (node (ref "C18") (pin "2") (pinfunction "2_2") (pintype "passive"))
      (node (ref "C19") (pin "2") (pinfunction "2_2") (pintype "passive"))
      (node (ref "C2") (pin "2") (pinfunction "2_2") (pintype "passive"))
      (node (ref "C20") (pin "2") (pinfunction "2_2") (pintype "passive"))
      (node (ref "C21") (pin "2") (pinfunction "2_2") (pintype "passive"))
      (node (ref "C22") (pin "2") (pinfunction "2_2") (pintype "passive"))
      (node (ref "C23") (pin "2") (pinfunction "2_2") (pintype "passive"))
      (node (ref "C24") (pin "2") (pinfunction "2_2") (pintype "passive"))
      (node (ref "C25") (pin "2") (pinfunction "2_2") (pintype "passive"))
      (node (ref "C26") (pin "1") (pinfunction "1_1") (pintype "passive"))
      (node (ref "C27") (pin "1") (pinfunction "1_1") (pintype "passive"))
      (node (ref "C28") (pin "1") (pinfunction "1_1") (pintype "passive"))
      (node (ref "C29") (pin "1") (pinfunction "1_1") (pintype "passive"))
      (node (ref "C3") (pin "1") (pinfunction "1_1") (pintype "passive"))
      (node (ref "C30") (pin "1") (pinfunction "1_1") (pintype "passive"))
      (node (ref "C31") (pin "1") (pinfunction "1_1") (pintype "passive"))
      (node (ref "C32") (pin "1") (pinfunction "1_1") (pintype "passive"))
      (node (ref "C33") (pin "1") (pinfunction "1_1") (pintype "passive"))
      (node (ref "C4") (pin "2") (pinfunction "2_2") (pintype "passive"))
      (node (ref "C5") (pin "2") (pinfunction "2_2") (pintype "passive"))
      (node (ref "C7") (pin "2") (pinfunction "2_2") (pintype "passive"))
      (node (ref "C8") (pin "1") (pinfunction "1_1") (pintype "passive"))
      (node (ref "DBUS") (pin "3") (pinfunction "3_3") (pintype "passive"))
      (node (ref "E1") (pin "2") (pinfunction "K_2") (pintype "passive"))
      (node (ref "GND") (pin "1") (pinfunction "1_1") (pintype "passive"))
      (node (ref "GND") (pin "2") (pinfunction "2_2") (pintype "passive"))
      (node (ref "GND") (pin "3") (pinfunction "3_3") (pintype "passive"))
      (node (ref "GND") (pin "4") (pinfunction "4_4") (pintype "passive"))
      (node (ref "GND") (pin "5") (pinfunction "5_5") (pintype "passive"))
      (node (ref "GND") (pin "6") (pinfunction "6_6") (pintype "passive"))
      (node (ref "IIC") (pin "1") (pinfunction "1_1") (pintype "passive"))
      (node (ref "LED2") (pin "2") (pinfunction "K_2") (pintype "passive"))
      (node (ref "LED3") (pin "2") (pinfunction "K_2") (pintype "passive"))
      (node (ref "LED4") (pin "2") (pinfunction "K_2") (pintype "passive"))
      (node (ref "POWER") (pin "2") (pinfunction "2_2") (pintype "passive"))
      (node (ref "Q1") (pin "2") (pinfunction "E_2") (pintype "passive"))
      (node (ref "Q2") (pin "2") (pinfunction "E_2") (pintype "passive"))
      (node (ref "Q3") (pin "2") (pinfunction "S_2") (pintype "passive"))
      (node (ref "R11") (pin "2") (pinfunction "2_2") (pintype "passive"))
      (node (ref "R12") (pin "1") (pinfunction "1_1") (pintype "passive"))
      (node (ref "R13") (pin "2") (pinfunction "2_2") (pintype "passive"))
      (node (ref "R17") (pin "2") (pinfunction "2_2") (pintype "passive"))
      (node (ref "R2") (pin "1") (pinfunction "1_1") (pintype "passive"))
      (node (ref "R23") (pin "1") (pinfunction "1_1") (pintype "passive"))
      (node (ref "R31") (pin "1") (pinfunction "1_1") (pintype "passive"))
      (node (ref "R4") (pin "2") (pinfunction "2_2") (pintype "passive"))
      (node (ref "R7") (pin "2") (pinfunction "2_2") (pintype "passive"))
      (node (ref "R9") (pin "2") (pinfunction "2_2") (pintype "passive"))
      (node (ref "REST1") (pin "2") (pinfunction "2_2") (pintype "passive"))
      (node (ref "SUPERCAP") (pin "6") (pinfunction "6_6") (pintype "passive"))
      (node (ref "SUPERCAP") (pin "7") (pinfunction "7_7") (pintype "passive"))
      (node (ref "SUPERCAP") (pin "8") (pinfunction "8_8") (pintype "passive"))
      (node (ref "SWD") (pin "3") (pinfunction "3_3") (pintype "passive"))
      (node (ref "U1") (pin "12") (pinfunction "VSSA_12") (pintype "power_in"))
      (node (ref "U1") (pin "18") (pinfunction "VSS_18") (pintype "power_in"))
      (node (ref "U1") (pin "63") (pinfunction "VSS_63") (pintype "power_in"))
      (node (ref "U2") (pin "4") (pinfunction "GND_4") (pintype "passive"))
      (node (ref "U3") (pin "3") (pinfunction "GND_3") (pintype "passive"))
      (node (ref "U3") (pin "4") (pinfunction "GND_4") (pintype "passive"))
      (node (ref "U4") (pin "1") (pinfunction "GND_1") (pintype "passive"))
      (node (ref "U5") (pin "11") (pinfunction "GND_11") (pintype "passive"))
      (node (ref "U5") (pin "9") (pinfunction "GND_9") (pintype "passive"))
      (node (ref "U6") (pin "10") (pinfunction "RESV_10") (pintype "passive"))
      (node (ref "U6") (pin "11") (pinfunction "RESV_11") (pintype "passive"))
      (node (ref "U6") (pin "12") (pinfunction "RESV_12") (pintype "passive"))
      (node (ref "U6") (pin "13") (pinfunction "GND_13") (pintype "passive"))
      (node (ref "U6") (pin "15") (pinfunction "RESV_15") (pintype "passive"))
      (node (ref "U6") (pin "8") (pinfunction "FSYNC_8") (pintype "passive"))
      (node (ref "U6") (pin "9") (pinfunction "RESV_9") (pintype "passive"))
      (node (ref "U7") (pin "1") (pinfunction "GND_1") (pintype "passive"))
      (node (ref "U7") (pin "7") (pinfunction "GND_7") (pintype "passive"))
      (node (ref "U8") (pin "2") (pinfunction "GND_2") (pintype "power_in"))
      (node (ref "U8") (pin "5") (pinfunction "SHDN_5") (pintype "input"))
      (node (ref "U8") (pin "8") (pinfunction "RS_8") (pintype "input"))
      (node (ref "U9") (pin "2") (pinfunction "GND_2") (pintype "power_in"))
      (node (ref "U9") (pin "5") (pinfunction "SHDN_5") (pintype "input"))
      (node (ref "U9") (pin "8") (pinfunction "RS_8") (pintype "input"))
      (node (ref "UART1") (pin "3") (pinfunction "3_3") (pintype "passive"))
      (node (ref "UART4") (pin "1") (pinfunction "1_1") (pintype "passive"))
      (node (ref "UART5") (pin "1") (pinfunction "1_1") (pintype "passive"))
      (node (ref "USART3") (pin "1") (pinfunction "1_1") (pintype "passive"))
      (node (ref "USART6") (pin "1") (pinfunction "1_1") (pintype "passive"))
      (node (ref "USB1") (pin "0") (pinfunction "0_0") (pintype "passive"))
      (node (ref "USB1") (pin "A1") (pinfunction "GND_A1") (pintype "passive"))
      (node (ref "USB1") (pin "A12") (pinfunction "GND_A12") (pintype "passive"))
      (node (ref "USB1") (pin "B1") (pinfunction "GND_B1") (pintype "passive"))
      (node (ref "USB1") (pin "B12") (pinfunction "GND_B12") (pintype "passive"))
      (node (ref "X1") (pin "2") (pinfunction "2_2") (pintype "passive"))
      (node (ref "X1") (pin "4") (pinfunction "4_4") (pintype "passive"))
    )
    (net (code "61") (name "Net-(DBUS-Pad1)") (class "Default")
      (node (ref "DBUS") (pin "1") (pinfunction "1_1") (pintype "passive"))
      (node (ref "R5") (pin "1") (pinfunction "1_1") (pintype "passive"))
    )
    (net (code "62") (name "Net-(LED1-K)") (class "Default")
      (node (ref "LED1") (pin "2") (pinfunction "K_2") (pintype "passive"))
      (node (ref "R13") (pin "1") (pinfunction "1_1") (pintype "passive"))
    )
    (net (code "63") (name "Net-(LED2-A)") (class "Default")
      (node (ref "LED2") (pin "1") (pinfunction "A_1") (pintype "passive"))
      (node (ref "R14") (pin "1") (pinfunction "1_1") (pintype "passive"))
    )
    (net (code "64") (name "Net-(LED3-A)") (class "Default")
      (node (ref "LED3") (pin "1") (pinfunction "A_1") (pintype "passive"))
      (node (ref "R15") (pin "1") (pinfunction "1_1") (pintype "passive"))
    )
    (net (code "65") (name "Net-(LED4-A)") (class "Default")
      (node (ref "LED4") (pin "1") (pinfunction "A_1") (pintype "passive"))
      (node (ref "R18") (pin "1") (pinfunction "1_1") (pintype "passive"))
    )
    (net (code "66") (name "Net-(Q1-B)") (class "Default")
      (node (ref "Q1") (pin "1") (pinfunction "B_1") (pintype "passive"))
      (node (ref "R5") (pin "2") (pinfunction "2_2") (pintype "passive"))
    )
    (net (code "67") (name "Net-(Q2-B)") (class "Default")
      (node (ref "Q2") (pin "1") (pinfunction "B_1") (pintype "passive"))
      (node (ref "R23") (pin "2") (pinfunction "2_2") (pintype "passive"))
      (node (ref "R25") (pin "2") (pinfunction "2_2") (pintype "passive"))
    )
    (net (code "68") (name "Net-(Q2-C)") (class "Default")
      (node (ref "LESER") (pin "1") (pinfunction "1_1") (pintype "passive"))
      (node (ref "Q2") (pin "3") (pinfunction "C_3") (pintype "passive"))
    )
    (net (code "69") (name "Net-(Q3-D)") (class "Default")
      (node (ref "Q3") (pin "3") (pinfunction "D_3") (pintype "passive"))
      (node (ref "R32") (pin "2") (pinfunction "2_2") (pintype "passive"))
      (node (ref "R33") (pin "2") (pinfunction "2_2") (pintype "passive"))
    )
    (net (code "70") (name "Net-(Q3-G)") (class "Default")
      (node (ref "Q3") (pin "1") (pinfunction "G_1") (pintype "passive"))
      (node (ref "R30") (pin "2") (pinfunction "2_2") (pintype "passive"))
      (node (ref "R31") (pin "2") (pinfunction "2_2") (pintype "passive"))
    )
    (net (code "71") (name "Net-(U1-PB2{slash}BOOT1)") (class "Default")
      (node (ref "R12") (pin "2") (pinfunction "2_2") (pintype "passive"))
      (node (ref "U1") (pin "28") (pinfunction "PB2/BOOT1_28") (pintype "bidirectional"))
    )
    (net (code "72") (name "Net-(U1-PH0{slash}OSC_IN)") (class "Default")
      (node (ref "C1") (pin "2") (pinfunction "2_2") (pintype "passive"))
      (node (ref "U1") (pin "5") (pinfunction "PH0/OSC_IN_5") (pintype "input"))
      (node (ref "X1") (pin "1") (pinfunction "1_1") (pintype "passive"))
    )
    (net (code "73") (name "Net-(U1-PH1{slash}OS_OUT)") (class "Default")
      (node (ref "C3") (pin "2") (pinfunction "2_2") (pintype "passive"))
      (node (ref "U1") (pin "6") (pinfunction "PH1/OS_OUT_6") (pintype "input"))
      (node (ref "X1") (pin "3") (pinfunction "3_3") (pintype "passive"))
    )
    (net (code "74") (name "Net-(U1-VCAP_1)") (class "Default")
      (node (ref "C14") (pin "2") (pinfunction "2_2") (pintype "passive"))
      (node (ref "U1") (pin "31") (pinfunction "VCAP_1_31") (pintype "passive"))
    )
    (net (code "75") (name "Net-(U1-VCAP_2)") (class "Default")
      (node (ref "C7") (pin "1") (pinfunction "1_1") (pintype "passive"))
      (node (ref "U1") (pin "47") (pinfunction "VCAP_2_47") (pintype "passive"))
    )
    (net (code "76") (name "Net-(U1-VDDA)") (class "Default")
      (node (ref "C4") (pin "1") (pinfunction "1_1") (pintype "passive"))
      (node (ref "C5") (pin "1") (pinfunction "1_1") (pintype "passive"))
      (node (ref "L1") (pin "2") (pinfunction "2_2") (pintype "passive"))
      (node (ref "U1") (pin "13") (pinfunction "VDDA_13") (pintype "power_in"))
    )
    (net (code "77") (name "Net-(U3-BS)") (class "Default")
      (node (ref "C9") (pin "2") (pinfunction "2_2") (pintype "passive"))
      (node (ref "U3") (pin "7") (pinfunction "BS_7") (pintype "passive"))
    )
    (net (code "78") (name "Net-(U3-EN)") (class "Default")
      (node (ref "R7") (pin "1") (pinfunction "1_1") (pintype "passive"))
      (node (ref "R8") (pin "2") (pinfunction "2_2") (pintype "passive"))
      (node (ref "U3") (pin "8") (pinfunction "EN_8") (pintype "passive"))
    )
    (net (code "79") (name "Net-(U3-FB)") (class "Default")
      (node (ref "C6") (pin "2") (pinfunction "2_2") (pintype "passive"))
      (node (ref "R10") (pin "2") (pinfunction "2_2") (pintype "passive"))
      (node (ref "R9") (pin "1") (pinfunction "1_1") (pintype "passive"))
      (node (ref "U3") (pin "1") (pinfunction "FB_1") (pintype "passive"))
    )
    (net (code "80") (name "Net-(U3-FS)") (class "Default")
      (node (ref "R11") (pin "1") (pinfunction "1_1") (pintype "passive"))
      (node (ref "U3") (pin "2") (pinfunction "FS_2") (pintype "passive"))
    )
    (net (code "81") (name "Net-(U3-LX)") (class "Default")
      (node (ref "C9") (pin "1") (pinfunction "1_1") (pintype "passive"))
      (node (ref "L2") (pin "1") (pinfunction "1_1") (pintype "passive"))
      (node (ref "U3") (pin "6") (pinfunction "LX_6") (pintype "passive"))
    )
    (net (code "82") (name "Net-(U5-C1)") (class "Default")
      (node (ref "C33") (pin "2") (pinfunction "2_2") (pintype "passive"))
      (node (ref "U5") (pin "10") (pinfunction "C1_10") (pintype "passive"))
    )
    (net (code "83") (name "Net-(U6-REGOUT)") (class "Default")
      (node (ref "C25") (pin "1") (pinfunction "1_1") (pintype "passive"))
      (node (ref "U6") (pin "14") (pinfunction "REGOUT_14") (pintype "passive"))
    )
    (net (code "84") (name "VUSB") (class "Default")
      (node (ref "D1") (pin "1") (pinfunction "A_1") (pintype "passive"))
      (node (ref "R24") (pin "2") (pinfunction "2_2") (pintype "passive"))
      (node (ref "USB1") (pin "A4") (pinfunction "VBUS_A4") (pintype "passive"))
      (node (ref "USB1") (pin "A9") (pinfunction "VBUS_A9") (pintype "passive"))
      (node (ref "USB1") (pin "B4") (pinfunction "VBUS_B4") (pintype "passive"))
      (node (ref "USB1") (pin "B9") (pinfunction "VBUS_B9") (pintype "passive"))
    )
    (net (code "85") (name "unconnected-(H1-Pad1)") (class "Default")
      (node (ref "H1") (pin "1") (pinfunction "1_1") (pintype "passive"))
    )
    (net (code "86") (name "unconnected-(H2-Pad1)") (class "Default")
      (node (ref "H2") (pin "1") (pinfunction "1_1") (pintype "passive"))
    )
    (net (code "87") (name "unconnected-(H3-Pad1)") (class "Default")
      (node (ref "H3") (pin "1") (pinfunction "1_1") (pintype "passive"))
    )
    (net (code "88") (name "unconnected-(H4-Pad1)") (class "Default")
      (node (ref "H4") (pin "1") (pinfunction "1_1") (pintype "passive"))
    )
    (net (code "89") (name "unconnected-(U5-CAD0-Pad5)") (class "Default")
      (node (ref "U5") (pin "5") (pinfunction "CAD0_5") (pintype "passive+no_connect"))
    )
    (net (code "90") (name "unconnected-(U5-CAD1-Pad6)") (class "Default")
      (node (ref "U5") (pin "6") (pinfunction "CAD1_6") (pintype "passive+no_connect"))
    )
    (net (code "91") (name "unconnected-(U5-NC-Pad3)") (class "Default")
      (node (ref "U5") (pin "3") (pinfunction "NC_3") (pintype "passive+no_connect"))
    )
    (net (code "92") (name "unconnected-(U5-NC-Pad4)") (class "Default")
      (node (ref "U5") (pin "4") (pinfunction "NC_4") (pintype "passive+no_connect"))
    )
    (net (code "93") (name "unconnected-(U5-NC-Pad8)") (class "Default")
      (node (ref "U5") (pin "8") (pinfunction "NC_8") (pintype "passive+no_connect"))
    )
    (net (code "94") (name "unconnected-(U5-NC-Pad12)") (class "Default")
      (node (ref "U5") (pin "12") (pinfunction "NC_12") (pintype "passive+no_connect"))
    )
    (net (code "95") (name "unconnected-(U5-VPP-Pad7)") (class "Default")
      (node (ref "U5") (pin "7") (pinfunction "VPP_7") (pintype "passive+no_connect"))
    )
    (net (code "96") (name "unconnected-(U6-RESV-Pad7)") (class "Default")
      (node (ref "U6") (pin "7") (pinfunction "RESV_7") (pintype "passive+no_connect"))
    )
    (net (code "97") (name "unconnected-(U7-CSB-Pad2)") (class "Default")
      (node (ref "U7") (pin "2") (pinfunction "CSB_2") (pintype "passive+no_connect"))
    )
    (net (code "98") (name "unconnected-(U7-SDO-Pad5)") (class "Default")
      (node (ref "U7") (pin "5") (pinfunction "SDO_5") (pintype "passive+no_connect"))
    )
    (net (code "99") (name "unconnected-(USB1-CC1-PadA5)") (class "Default")
      (node (ref "USB1") (pin "A5") (pinfunction "CC1_A5") (pintype "passive+no_connect"))
    )
    (net (code "100") (name "unconnected-(USB1-CC2-PadB5)") (class "Default")
      (node (ref "USB1") (pin "B5") (pinfunction "CC2_B5") (pintype "passive+no_connect"))
    )
    (net (code "101") (name "unconnected-(USB1-SBU2-PadB8)") (class "Default")
      (node (ref "USB1") (pin "B8") (pinfunction "SBU2_B8") (pintype "passive+no_connect"))
    )
    (net (code "102") (name "unconnected-(USB1-SUB1-PadA8)") (class "Default")
      (node (ref "USB1") (pin "A8") (pinfunction "SUB1_A8") (pintype "passive+no_connect"))
    )
  )
)
